# usb-sanitizer.net
KiCad netlist of a schematic drawn in EAGLE
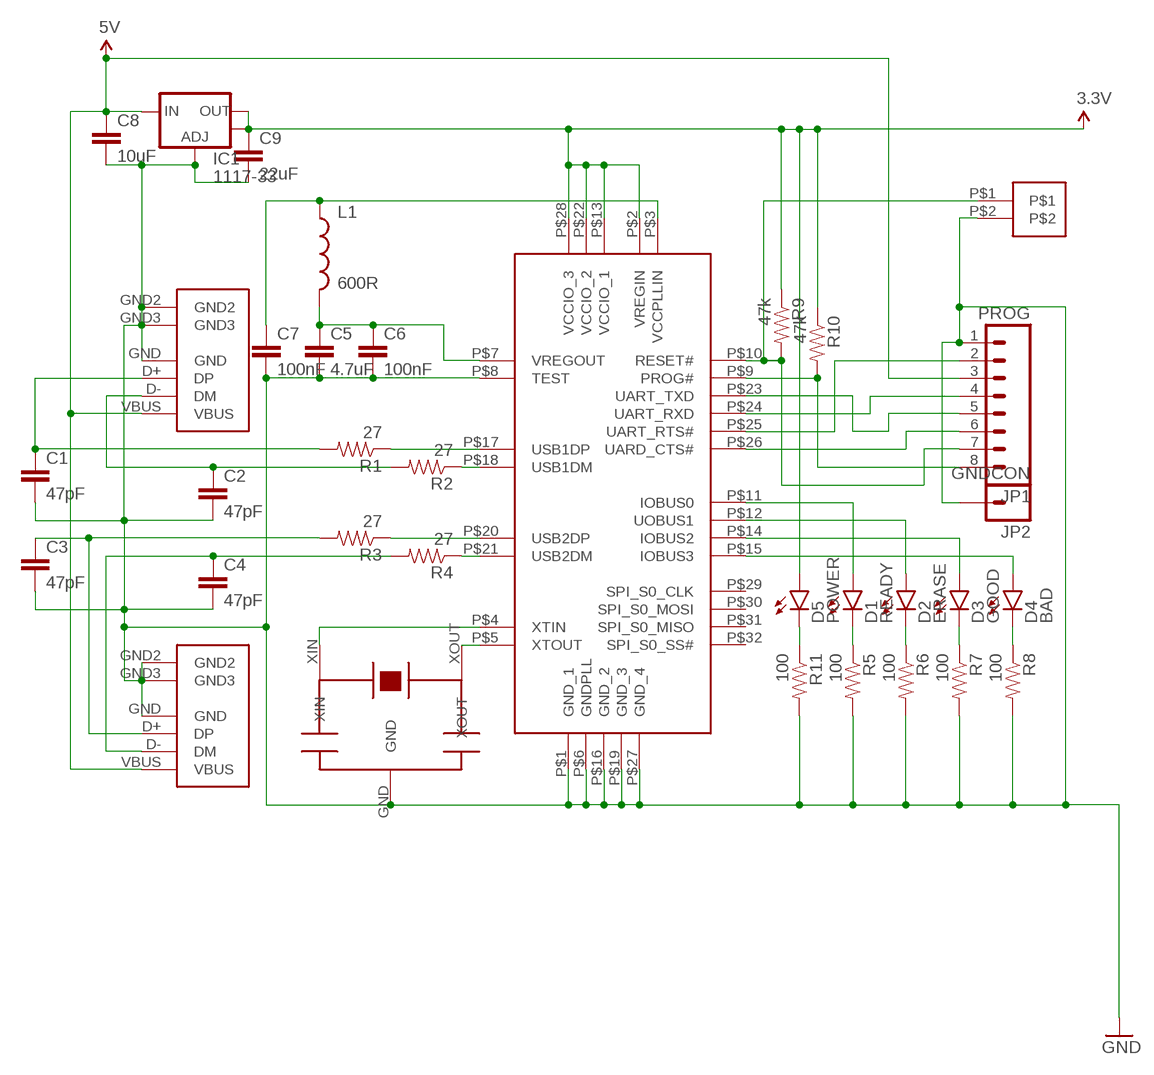
[diagram p0: schematic, sheet 1]

(export (version "E")
  (design (tool "Eeschema 10.0.6"))
  (components
    (comp (ref "C1")
      (value "47pF")
      (footprint "eagle-import:0805")
      (libsource (lib "eagle-import") (part "CAP0805"))
    )
    (comp (ref "C2")
      (value "47pF")
      (footprint "eagle-import:0805")
      (libsource (lib "eagle-import") (part "CAP0805"))
    )
    (comp (ref "C3")
      (value "47pF")
      (footprint "eagle-import:0805")
      (libsource (lib "eagle-import") (part "CAP0805"))
    )
    (comp (ref "C4")
      (value "47pF")
      (footprint "eagle-import:0805")
      (libsource (lib "eagle-import") (part "CAP0805"))
    )
    (comp (ref "C5")
      (value "4.7uF")
      (footprint "eagle-import:0805")
      (libsource (lib "eagle-import") (part "CAP0805"))
    )
    (comp (ref "C6")
      (value "100nF")
      (footprint "eagle-import:0805")
      (libsource (lib "eagle-import") (part "CAP0805"))
    )
    (comp (ref "C7")
      (value "100nF")
      (footprint "eagle-import:0805")
      (libsource (lib "eagle-import") (part "CAP0805"))
    )
    (comp (ref "C8")
      (value "10uF")
      (footprint "eagle-import:0805")
      (libsource (lib "eagle-import") (part "CAP0805"))
    )
    (comp (ref "C9")
      (value "22uF")
      (footprint "eagle-import:0805")
      (libsource (lib "eagle-import") (part "CAP0805"))
    )
    (comp (ref "D1")
      (value "READY")
      (footprint "eagle-import:0805")
      (libsource (lib "eagle-import") (part "LED-0805"))
    )
    (comp (ref "D2")
      (value "ERASE")
      (footprint "eagle-import:0805")
      (libsource (lib "eagle-import") (part "LED-0805"))
    )
    (comp (ref "D3")
      (value "GOOD")
      (footprint "eagle-import:0805")
      (libsource (lib "eagle-import") (part "LED-0805"))
    )
    (comp (ref "D4")
      (value "BAD")
      (footprint "eagle-import:0805")
      (libsource (lib "eagle-import") (part "LED-0805"))
    )
    (comp (ref "D5")
      (value "POWER")
      (footprint "eagle-import:0805")
      (libsource (lib "eagle-import") (part "LED-0805"))
    )
    (comp (ref "IC1")
      (value "1117-33")
      (footprint "eagle-import:SOT223")
      (libsource (lib "eagle-import") (part "V_REG_LM1117SOT223"))
    )
    (comp (ref "JP1")
      (value "PROG")
      (footprint "eagle-import:1X08_LOCK")
      (libsource (lib "eagle-import") (part "M08LOCK"))
    )
    (comp (ref "JP2")
      (value "GNDCON")
      (footprint "eagle-import:1X01")
      (libsource (lib "eagle-import") (part "M01PTH"))
    )
    (comp (ref "L1")
      (value "600R")
      (footprint "eagle-import:0805")
      (libsource (lib "eagle-import") (part "INDUCTOR0805"))
    )
    (comp (ref "R1")
      (value "27")
      (footprint "eagle-import:0805")
      (libsource (lib "eagle-import") (part "RESISTOR0805-RES"))
    )
    (comp (ref "R2")
      (value "27")
      (footprint "eagle-import:0805")
      (libsource (lib "eagle-import") (part "RESISTOR0805-RES"))
    )
    (comp (ref "R3")
      (value "27")
      (footprint "eagle-import:0805")
      (libsource (lib "eagle-import") (part "RESISTOR0805-RES"))
    )
    (comp (ref "R4")
      (value "27")
      (footprint "eagle-import:0805")
      (libsource (lib "eagle-import") (part "RESISTOR0805-RES"))
    )
    (comp (ref "R5")
      (value "100")
      (footprint "eagle-import:0805")
      (libsource (lib "eagle-import") (part "RESISTOR0805-RES"))
    )
    (comp (ref "R6")
      (value "100")
      (footprint "eagle-import:0805")
      (libsource (lib "eagle-import") (part "RESISTOR0805-RES"))
    )
    (comp (ref "R7")
      (value "100")
      (footprint "eagle-import:0805")
      (libsource (lib "eagle-import") (part "RESISTOR0805-RES"))
    )
    (comp (ref "R8")
      (value "100")
      (footprint "eagle-import:0805")
      (libsource (lib "eagle-import") (part "RESISTOR0805-RES"))
    )
    (comp (ref "R9")
      (value "47k")
      (footprint "eagle-import:0805")
      (libsource (lib "eagle-import") (part "RESISTOR0805-RES"))
    )
    (comp (ref "R10")
      (value "47k")
      (footprint "eagle-import:0805")
      (libsource (lib "eagle-import") (part "RESISTOR0805-RES"))
    )
    (comp (ref "R11")
      (value "100")
      (footprint "eagle-import:0805")
      (libsource (lib "eagle-import") (part "RESISTOR0805-RES"))
    )
    (comp (ref "U$1")
      (value "VNC2")
      (footprint "eagle-import:QFP32")
      (libsource (lib "eagle-import") (part "VNC2"))
    )
    (comp (ref "U$4")
      (value "RESONATOR")
      (footprint "eagle-import:RESONATOR")
      (libsource (lib "eagle-import") (part "RESONATOR"))
    )
    (comp (ref "U$5")
      (value "SWITCH")
      (footprint "eagle-import:SWITCH")
      (libsource (lib "eagle-import") (part "SWITCH"))
    )
    (comp (ref "USB_FEMALE")
      (value "USB_AF")
      (footprint "eagle-import:USB-A-F")
      (libsource (lib "eagle-import") (part "USB_AF"))
    )
    (comp (ref "USB_MALE")
      (value "USB_AM")
      (footprint "eagle-import:USB-A-M")
      (libsource (lib "eagle-import") (part "USB_AM"))
    )
  )
  (nets
    (net (code "1") (name "3.3V") (class "Default")
      (node (ref "C9") (pin "1") (pinfunction "1_1") (pintype "passive"))
      (node (ref "D5") (pin "1") (pinfunction "A_1") (pintype "passive"))
      (node (ref "IC1") (pin "2") (pinfunction "OUT_2") (pintype "output"))
      (node (ref "IC1") (pin "4") (pinfunction "OUT_4") (pintype "output"))
      (node (ref "R10") (pin "1") (pinfunction "1_1") (pintype "passive"))
      (node (ref "R9") (pin "1") (pinfunction "1_1") (pintype "passive"))
      (node (ref "U$1") (pin "P$13") (pinfunction "VCCIO_1_P$13") (pintype "bidirectional"))
      (node (ref "U$1") (pin "P$2") (pinfunction "VREGIN_P$2") (pintype "bidirectional"))
      (node (ref "U$1") (pin "P$22") (pinfunction "VCCIO_2_P$22") (pintype "bidirectional"))
      (node (ref "U$1") (pin "P$28") (pinfunction "VCCIO_3_P$28") (pintype "bidirectional"))
    )
    (net (code "2") (name "5V") (class "Default")
      (node (ref "C8") (pin "1") (pinfunction "1_1") (pintype "passive"))
      (node (ref "IC1") (pin "3") (pinfunction "IN_3") (pintype "input"))
      (node (ref "JP1") (pin "3") (pinfunction "3_3") (pintype "passive"))
      (node (ref "USB_FEMALE") (pin "VBUS") (pinfunction "VBUS_VBUS") (pintype "bidirectional"))
      (node (ref "USB_MALE") (pin "VBUS") (pinfunction "VBUS_VBUS") (pintype "bidirectional"))
    )
    (net (code "3") (name "GND") (class "Default")
      (node (ref "C1") (pin "2") (pinfunction "2_2") (pintype "passive"))
      (node (ref "C2") (pin "2") (pinfunction "2_2") (pintype "passive"))
      (node (ref "C3") (pin "2") (pinfunction "2_2") (pintype "passive"))
      (node (ref "C4") (pin "2") (pinfunction "2_2") (pintype "passive"))
      (node (ref "C5") (pin "2") (pinfunction "2_2") (pintype "passive"))
      (node (ref "C6") (pin "2") (pinfunction "2_2") (pintype "passive"))
      (node (ref "C7") (pin "2") (pinfunction "2_2") (pintype "passive"))
      (node (ref "C8") (pin "2") (pinfunction "2_2") (pintype "passive"))
      (node (ref "C9") (pin "2") (pinfunction "2_2") (pintype "passive"))
      (node (ref "IC1") (pin "1") (pinfunction "ADJ_1") (pintype "input"))
      (node (ref "JP1") (pin "1") (pinfunction "1_1") (pintype "passive"))
      (node (ref "JP2") (pin "1") (pinfunction "1_1") (pintype "passive"))
      (node (ref "R11") (pin "2") (pinfunction "2_2") (pintype "passive"))
      (node (ref "R5") (pin "2") (pinfunction "2_2") (pintype "passive"))
      (node (ref "R6") (pin "2") (pinfunction "2_2") (pintype "passive"))
      (node (ref "R7") (pin "2") (pinfunction "2_2") (pintype "passive"))
      (node (ref "R8") (pin "2") (pinfunction "2_2") (pintype "passive"))
      (node (ref "U$1") (pin "P$1") (pinfunction "GND_1_P$1") (pintype "bidirectional"))
      (node (ref "U$1") (pin "P$16") (pinfunction "GND_2_P$16") (pintype "bidirectional"))
      (node (ref "U$1") (pin "P$19") (pinfunction "GND_3_P$19") (pintype "bidirectional"))
      (node (ref "U$1") (pin "P$27") (pinfunction "GND_4_P$27") (pintype "bidirectional"))
      (node (ref "U$1") (pin "P$6") (pinfunction "GNDPLL_P$6") (pintype "bidirectional"))
      (node (ref "U$1") (pin "P$8") (pinfunction "TEST_P$8") (pintype "bidirectional"))
      (node (ref "U$4") (pin "GND") (pinfunction "GND_GND") (pintype "bidirectional"))
      (node (ref "U$5") (pin "P$2") (pinfunction "P$2_P$2") (pintype "bidirectional"))
      (node (ref "USB_FEMALE") (pin "GND") (pinfunction "GND_GND") (pintype "bidirectional"))
      (node (ref "USB_FEMALE") (pin "GND2") (pinfunction "GND2_GND2") (pintype "bidirectional"))
      (node (ref "USB_FEMALE") (pin "GND3") (pinfunction "GND3_GND3") (pintype "bidirectional"))
      (node (ref "USB_MALE") (pin "GND") (pinfunction "GND_GND") (pintype "bidirectional"))
      (node (ref "USB_MALE") (pin "GND2") (pinfunction "GND2_GND2") (pintype "bidirectional"))
      (node (ref "USB_MALE") (pin "GND3") (pinfunction "GND3_GND3") (pintype "bidirectional"))
    )
    (net (code "4") (name "Net-(D1-A)") (class "Default")
      (node (ref "D1") (pin "1") (pinfunction "A_1") (pintype "passive"))
      (node (ref "U$1") (pin "P$11") (pinfunction "IOBUS0_P$11") (pintype "bidirectional"))
    )
    (net (code "5") (name "Net-(D1-C)") (class "Default")
      (node (ref "D1") (pin "2") (pinfunction "C_2") (pintype "passive"))
      (node (ref "R5") (pin "1") (pinfunction "1_1") (pintype "passive"))
    )
    (net (code "6") (name "Net-(D2-A)") (class "Default")
      (node (ref "D2") (pin "1") (pinfunction "A_1") (pintype "passive"))
      (node (ref "U$1") (pin "P$12") (pinfunction "UOBUS1_P$12") (pintype "bidirectional"))
    )
    (net (code "7") (name "Net-(D2-C)") (class "Default")
      (node (ref "D2") (pin "2") (pinfunction "C_2") (pintype "passive"))
      (node (ref "R6") (pin "1") (pinfunction "1_1") (pintype "passive"))
    )
    (net (code "8") (name "Net-(D3-A)") (class "Default")
      (node (ref "D3") (pin "1") (pinfunction "A_1") (pintype "passive"))
      (node (ref "U$1") (pin "P$14") (pinfunction "IOBUS2_P$14") (pintype "bidirectional"))
    )
    (net (code "9") (name "Net-(D3-C)") (class "Default")
      (node (ref "D3") (pin "2") (pinfunction "C_2") (pintype "passive"))
      (node (ref "R7") (pin "1") (pinfunction "1_1") (pintype "passive"))
    )
    (net (code "10") (name "Net-(D4-A)") (class "Default")
      (node (ref "D4") (pin "1") (pinfunction "A_1") (pintype "passive"))
      (node (ref "U$1") (pin "P$15") (pinfunction "IOBUS3_P$15") (pintype "bidirectional"))
    )
    (net (code "11") (name "Net-(D4-C)") (class "Default")
      (node (ref "D4") (pin "2") (pinfunction "C_2") (pintype "passive"))
      (node (ref "R8") (pin "1") (pinfunction "1_1") (pintype "passive"))
    )
    (net (code "12") (name "Net-(D5-C)") (class "Default")
      (node (ref "D5") (pin "2") (pinfunction "C_2") (pintype "passive"))
      (node (ref "R11") (pin "1") (pinfunction "1_1") (pintype "passive"))
    )
    (net (code "13") (name "Net-(U$1-PROG#)") (class "Default")
      (node (ref "JP1") (pin "8") (pinfunction "8_8") (pintype "passive"))
      (node (ref "R10") (pin "2") (pinfunction "2_2") (pintype "passive"))
      (node (ref "U$1") (pin "P$9") (pinfunction "PROG#_P$9") (pintype "bidirectional"))
    )
    (net (code "14") (name "Net-(U$1-RESET#)") (class "Default")
      (node (ref "JP1") (pin "7") (pinfunction "7_7") (pintype "passive"))
      (node (ref "R9") (pin "2") (pinfunction "2_2") (pintype "passive"))
      (node (ref "U$1") (pin "P$10") (pinfunction "RESET#_P$10") (pintype "bidirectional"))
      (node (ref "U$5") (pin "P$1") (pinfunction "P$1_P$1") (pintype "bidirectional"))
    )
    (net (code "15") (name "Net-(U$1-UARD_CTS#)") (class "Default")
      (node (ref "JP1") (pin "6") (pinfunction "6_6") (pintype "passive"))
      (node (ref "U$1") (pin "P$26") (pinfunction "UARD_CTS#_P$26") (pintype "bidirectional"))
    )
    (net (code "16") (name "Net-(U$1-UART_RTS#)") (class "Default")
      (node (ref "JP1") (pin "2") (pinfunction "2_2") (pintype "passive"))
      (node (ref "U$1") (pin "P$25") (pinfunction "UART_RTS#_P$25") (pintype "bidirectional"))
    )
    (net (code "17") (name "Net-(U$1-UART_RXD)") (class "Default")
      (node (ref "JP1") (pin "4") (pinfunction "4_4") (pintype "passive"))
      (node (ref "U$1") (pin "P$24") (pinfunction "UART_RXD_P$24") (pintype "bidirectional"))
    )
    (net (code "18") (name "Net-(U$1-UART_TXD)") (class "Default")
      (node (ref "JP1") (pin "5") (pinfunction "5_5") (pintype "passive"))
      (node (ref "U$1") (pin "P$23") (pinfunction "UART_TXD_P$23") (pintype "bidirectional"))
    )
    (net (code "19") (name "Net-(U$1-USB1DM)") (class "Default")
      (node (ref "R2") (pin "1") (pinfunction "1_1") (pintype "passive"))
      (node (ref "U$1") (pin "P$18") (pinfunction "USB1DM_P$18") (pintype "bidirectional"))
    )
    (net (code "20") (name "Net-(U$1-USB1DP)") (class "Default")
      (node (ref "R1") (pin "1") (pinfunction "1_1") (pintype "passive"))
      (node (ref "U$1") (pin "P$17") (pinfunction "USB1DP_P$17") (pintype "bidirectional"))
    )
    (net (code "21") (name "Net-(U$1-USB2DM)") (class "Default")
      (node (ref "R4") (pin "1") (pinfunction "1_1") (pintype "passive"))
      (node (ref "U$1") (pin "P$21") (pinfunction "USB2DM_P$21") (pintype "bidirectional"))
    )
    (net (code "22") (name "Net-(U$1-USB2DP)") (class "Default")
      (node (ref "R3") (pin "1") (pinfunction "1_1") (pintype "passive"))
      (node (ref "U$1") (pin "P$20") (pinfunction "USB2DP_P$20") (pintype "bidirectional"))
    )
    (net (code "23") (name "Net-(U$1-VCCPLLIN)") (class "Default")
      (node (ref "C7") (pin "1") (pinfunction "1_1") (pintype "passive"))
      (node (ref "L1") (pin "1") (pinfunction "1_1") (pintype "passive"))
      (node (ref "U$1") (pin "P$3") (pinfunction "VCCPLLIN_P$3") (pintype "bidirectional"))
    )
    (net (code "24") (name "Net-(U$1-VREGOUT)") (class "Default")
      (node (ref "C5") (pin "1") (pinfunction "1_1") (pintype "passive"))
      (node (ref "C6") (pin "1") (pinfunction "1_1") (pintype "passive"))
      (node (ref "L1") (pin "2") (pinfunction "2_2") (pintype "passive"))
      (node (ref "U$1") (pin "P$7") (pinfunction "VREGOUT_P$7") (pintype "bidirectional"))
    )
    (net (code "25") (name "Net-(U$1-XTIN)") (class "Default")
      (node (ref "U$1") (pin "P$4") (pinfunction "XTIN_P$4") (pintype "bidirectional"))
      (node (ref "U$4") (pin "XIN") (pinfunction "XIN_XIN") (pintype "bidirectional"))
    )
    (net (code "26") (name "Net-(U$1-XTOUT)") (class "Default")
      (node (ref "U$1") (pin "P$5") (pinfunction "XTOUT_P$5") (pintype "bidirectional"))
      (node (ref "U$4") (pin "XOUT") (pinfunction "XOUT_XOUT") (pintype "bidirectional"))
    )
    (net (code "27") (name "Net-(USB_FEMALE-DM)") (class "Default")
      (node (ref "C2") (pin "1") (pinfunction "1_1") (pintype "passive"))
      (node (ref "R2") (pin "2") (pinfunction "2_2") (pintype "passive"))
      (node (ref "USB_FEMALE") (pin "D-") (pinfunction "DM_D-") (pintype "bidirectional"))
    )
    (net (code "28") (name "Net-(USB_FEMALE-DP)") (class "Default")
      (node (ref "C1") (pin "1") (pinfunction "1_1") (pintype "passive"))
      (node (ref "R1") (pin "2") (pinfunction "2_2") (pintype "passive"))
      (node (ref "USB_FEMALE") (pin "D+") (pinfunction "DP_D+") (pintype "bidirectional"))
    )
    (net (code "29") (name "Net-(USB_MALE-DM)") (class "Default")
      (node (ref "C4") (pin "1") (pinfunction "1_1") (pintype "passive"))
      (node (ref "R4") (pin "2") (pinfunction "2_2") (pintype "passive"))
      (node (ref "USB_MALE") (pin "D-") (pinfunction "DM_D-") (pintype "bidirectional"))
    )
    (net (code "30") (name "Net-(USB_MALE-DP)") (class "Default")
      (node (ref "C3") (pin "1") (pinfunction "1_1") (pintype "passive"))
      (node (ref "R3") (pin "2") (pinfunction "2_2") (pintype "passive"))
      (node (ref "USB_MALE") (pin "D+") (pinfunction "DP_D+") (pintype "bidirectional"))
    )
    (net (code "31") (name "unconnected-(U$1-SPI_S0_CLK-PadP$29)") (class "Default")
      (node (ref "U$1") (pin "P$29") (pinfunction "SPI_S0_CLK_P$29") (pintype "bidirectional"))
    )
    (net (code "32") (name "unconnected-(U$1-SPI_S0_MISO-PadP$31)") (class "Default")
      (node (ref "U$1") (pin "P$31") (pinfunction "SPI_S0_MISO_P$31") (pintype "bidirectional"))
    )
    (net (code "33") (name "unconnected-(U$1-SPI_S0_MOSI-PadP$30)") (class "Default")
      (node (ref "U$1") (pin "P$30") (pinfunction "SPI_S0_MOSI_P$30") (pintype "bidirectional"))
    )
    (net (code "34") (name "unconnected-(U$1-SPI_S0_SS#-PadP$32)") (class "Default")
      (node (ref "U$1") (pin "P$32") (pinfunction "SPI_S0_SS#_P$32") (pintype "bidirectional"))
    )
  )
)
